# intanRHS2116.net
KiCad netlist of a schematic drawn in Altium Designer
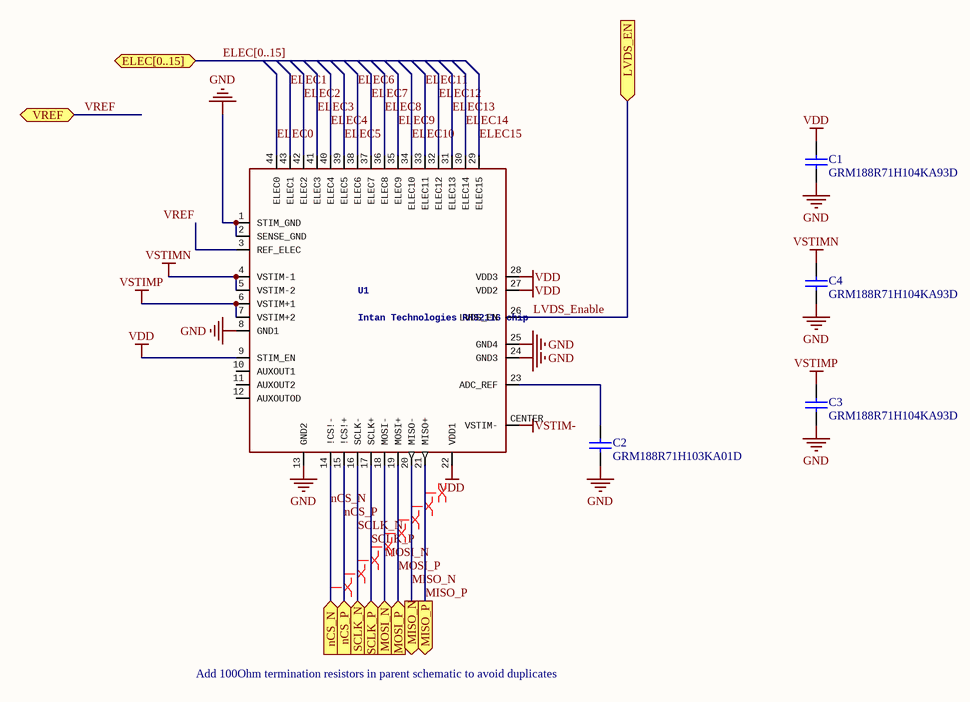
[diagram p0: intanRHS2116.SchDoc]

(export (version "E")
  (design (tool "Eeschema 10.0.6"))
  (components
    (comp (ref "C1")
      (value "GRM188R71H104KA93D")
      (footprint "CAPC1608X90X35ML10T15")
      (description "Chip Capacitor, 0.1 uF, +/- 10%, 50 V, -55 to 125 degC, 0603 (1608 Metric), RoHS, Tape and Reel")
      (fields (field (name "TOLERANCE") "10%") (field (name "VOLTAGE") "50V"))
      (libsource (lib "Altium Content Vault") (part "CAP-NP-2"))
    )
    (comp (ref "C2")
      (value "GRM188R71H103KA01D")
      (footprint "CAPC1608X90X35ML10T15")
      (description "Chip Capacitor, 10 nF, +/- 10%, 50 V, -55 to 125 degC, 0603 (1608 Metric), RoHS, Tape and Reel")
      (fields (field (name "VOLTAGE") "50V") (field (name "TOLERANCE") "10%"))
      (libsource (lib "Altium Content Vault") (part "CAP-NP-2"))
    )
    (comp (ref "C3")
      (value "GRM188R71H104KA93D")
      (footprint "CAPC1608X90X35ML10T15")
      (description "Chip Capacitor, 0.1 uF, +/- 10%, 50 V, -55 to 125 degC, 0603 (1608 Metric), RoHS, Tape and Reel")
      (fields (field (name "TOLERANCE") "10%") (field (name "VOLTAGE") "50V"))
      (libsource (lib "Altium Content Vault") (part "CAP-NP-2"))
    )
    (comp (ref "C4")
      (value "GRM188R71H104KA93D")
      (footprint "CAPC1608X90X35ML10T15")
      (description "Chip Capacitor, 0.1 uF, +/- 10%, 50 V, -55 to 125 degC, 0603 (1608 Metric), RoHS, Tape and Reel")
      (fields (field (name "TOLERANCE") "10%") (field (name "VOLTAGE") "50V"))
      (libsource (lib "Altium Content Vault") (part "CAP-NP-2"))
    )
    (comp (ref "U1")
      (value "Intan Technologies RHS2116 chip")
      (footprint "intan_rhs2116:QFN44_7_X_7")
      (fields
        (field (name "MANUFACTURER") "Intan Technologies")
        (field (name "MANUFACTURER PART NUMBER") "RHS2116")
      )
      (libsource (lib "intan_rhs2116") (part "RHS2116_QFN"))
    )
  )
  (nets
    (net (code "1") (name "/ELEC0") (class "Default")
      (node (ref "U1") (pin "44") (pinfunction "ELEC0_44") (pintype "passive"))
    )
    (net (code "2") (name "/ELEC1") (class "Default")
      (node (ref "U1") (pin "43") (pinfunction "ELEC1_43") (pintype "passive"))
    )
    (net (code "3") (name "/ELEC2") (class "Default")
      (node (ref "U1") (pin "42") (pinfunction "ELEC2_42") (pintype "passive"))
    )
    (net (code "4") (name "/ELEC3") (class "Default")
      (node (ref "U1") (pin "41") (pinfunction "ELEC3_41") (pintype "passive"))
    )
    (net (code "5") (name "/ELEC4") (class "Default")
      (node (ref "U1") (pin "40") (pinfunction "ELEC4_40") (pintype "passive"))
    )
    (net (code "6") (name "/ELEC5") (class "Default")
      (node (ref "U1") (pin "39") (pinfunction "ELEC5_39") (pintype "passive"))
    )
    (net (code "7") (name "/ELEC6") (class "Default")
      (node (ref "U1") (pin "38") (pinfunction "ELEC6_38") (pintype "passive"))
    )
    (net (code "8") (name "/ELEC7") (class "Default")
      (node (ref "U1") (pin "37") (pinfunction "ELEC7_37") (pintype "passive"))
    )
    (net (code "9") (name "/ELEC8") (class "Default")
      (node (ref "U1") (pin "36") (pinfunction "ELEC8_36") (pintype "passive"))
    )
    (net (code "10") (name "/ELEC9") (class "Default")
      (node (ref "U1") (pin "35") (pinfunction "ELEC9_35") (pintype "passive"))
    )
    (net (code "11") (name "/ELEC10") (class "Default")
      (node (ref "U1") (pin "34") (pinfunction "ELEC10_34") (pintype "passive"))
    )
    (net (code "12") (name "/ELEC11") (class "Default")
      (node (ref "U1") (pin "33") (pinfunction "ELEC11_33") (pintype "passive"))
    )
    (net (code "13") (name "/ELEC12") (class "Default")
      (node (ref "U1") (pin "32") (pinfunction "ELEC12_32") (pintype "passive"))
    )
    (net (code "14") (name "/ELEC13") (class "Default")
      (node (ref "U1") (pin "31") (pinfunction "ELEC13_31") (pintype "passive"))
    )
    (net (code "15") (name "/ELEC14") (class "Default")
      (node (ref "U1") (pin "30") (pinfunction "ELEC14_30") (pintype "passive"))
    )
    (net (code "16") (name "/ELEC15") (class "Default")
      (node (ref "U1") (pin "29") (pinfunction "ELEC15_29") (pintype "passive"))
    )
    (net (code "18") (name "/LVDS_Enable") (class "Default")
      (node (ref "U1") (pin "26") (pinfunction "LVDS_EN_26") (pintype "passive"))
    )
    (net (code "19") (name "/MISO_N") (class "Default")
      (node (ref "U1") (pin "20") (pinfunction "MISO-_20") (pintype "output"))
    )
    (net (code "20") (name "/MISO_P") (class "Default")
      (node (ref "U1") (pin "21") (pinfunction "MISO+_21") (pintype "output"))
    )
    (net (code "21") (name "/MOSI_N") (class "Default")
      (node (ref "U1") (pin "18") (pinfunction "MOSI-_18") (pintype "passive"))
    )
    (net (code "22") (name "/MOSI_P") (class "Default")
      (node (ref "U1") (pin "19") (pinfunction "MOSI+_19") (pintype "passive"))
    )
    (net (code "23") (name "/SCLK_N") (class "Default")
      (node (ref "U1") (pin "16") (pinfunction "SCLK-_16") (pintype "passive"))
    )
    (net (code "24") (name "/SCLK_P") (class "Default")
      (node (ref "U1") (pin "17") (pinfunction "SCLK+_17") (pintype "passive"))
    )
    (net (code "25") (name "/VREF") (class "Default")
      (node (ref "U1") (pin "3") (pinfunction "REF_ELEC_3") (pintype "passive"))
    )
    (net (code "26") (name "/nCS_N") (class "Default")
      (node (ref "U1") (pin "14") (pinfunction "!CS!-_14") (pintype "passive"))
    )
    (net (code "27") (name "/nCS_P") (class "Default")
      (node (ref "U1") (pin "15") (pinfunction "!CS!+_15") (pintype "passive"))
    )
    (net (code "28") (name "GND") (class "Default")
      (node (ref "C1") (pin "1") (pinfunction "1_1") (pintype "passive"))
      (node (ref "C2") (pin "1") (pinfunction "1_1") (pintype "passive"))
      (node (ref "C3") (pin "1") (pinfunction "1_1") (pintype "passive"))
      (node (ref "C4") (pin "1") (pinfunction "1_1") (pintype "passive"))
      (node (ref "U1") (pin "1") (pinfunction "STIM_GND_1") (pintype "power_in"))
      (node (ref "U1") (pin "13") (pinfunction "GND2_13") (pintype "power_in"))
      (node (ref "U1") (pin "2") (pinfunction "SENSE_GND_2") (pintype "power_in"))
      (node (ref "U1") (pin "24") (pinfunction "GND3_24") (pintype "power_in"))
      (node (ref "U1") (pin "25") (pinfunction "GND4_25") (pintype "power_in"))
      (node (ref "U1") (pin "8") (pinfunction "GND1_8") (pintype "power_in"))
    )
    (net (code "29") (name "Net-(U1-ADC_REF)") (class "Default")
      (node (ref "C2") (pin "2") (pinfunction "2_2") (pintype "passive"))
      (node (ref "U1") (pin "23") (pinfunction "ADC_REF_23") (pintype "passive"))
    )
    (net (code "30") (name "VDD") (class "Default")
      (node (ref "C1") (pin "2") (pinfunction "2_2") (pintype "passive"))
      (node (ref "U1") (pin "22") (pinfunction "VDD1_22") (pintype "power_in"))
      (node (ref "U1") (pin "27") (pinfunction "VDD2_27") (pintype "power_in"))
      (node (ref "U1") (pin "28") (pinfunction "VDD3_28") (pintype "power_in"))
      (node (ref "U1") (pin "9") (pinfunction "STIM_EN_9") (pintype "passive"))
    )
    (net (code "31") (name "VSTIM-") (class "Default")
      (node (ref "U1") (pin "CENTER") (pinfunction "VSTIM-_CENTER") (pintype "power_in"))
    )
    (net (code "32") (name "VSTIMN") (class "Default")
      (node (ref "C4") (pin "2") (pinfunction "2_2") (pintype "passive"))
      (node (ref "U1") (pin "4") (pinfunction "VSTIM-1_4") (pintype "power_in"))
      (node (ref "U1") (pin "5") (pinfunction "VSTIM-2_5") (pintype "power_in"))
    )
    (net (code "33") (name "VSTIMP") (class "Default")
      (node (ref "C3") (pin "2") (pinfunction "2_2") (pintype "passive"))
      (node (ref "U1") (pin "6") (pinfunction "VSTIM+1_6") (pintype "power_in"))
      (node (ref "U1") (pin "7") (pinfunction "VSTIM+2_7") (pintype "power_in"))
    )
    (net (code "34") (name "unconnected-(U1-AUXOUT1-Pad10)") (class "Default")
      (node (ref "U1") (pin "10") (pinfunction "AUXOUT1_10") (pintype "tri_state"))
    )
    (net (code "35") (name "unconnected-(U1-AUXOUT2-Pad11)") (class "Default")
      (node (ref "U1") (pin "11") (pinfunction "AUXOUT2_11") (pintype "tri_state"))
    )
    (net (code "36") (name "unconnected-(U1-AUXOUTOD-Pad12)") (class "Default")
      (node (ref "U1") (pin "12") (pinfunction "AUXOUTOD_12") (pintype "open_collector"))
    )
  )
)
